# Sheet1.net
KiCad netlist of a schematic drawn in Altium Designer
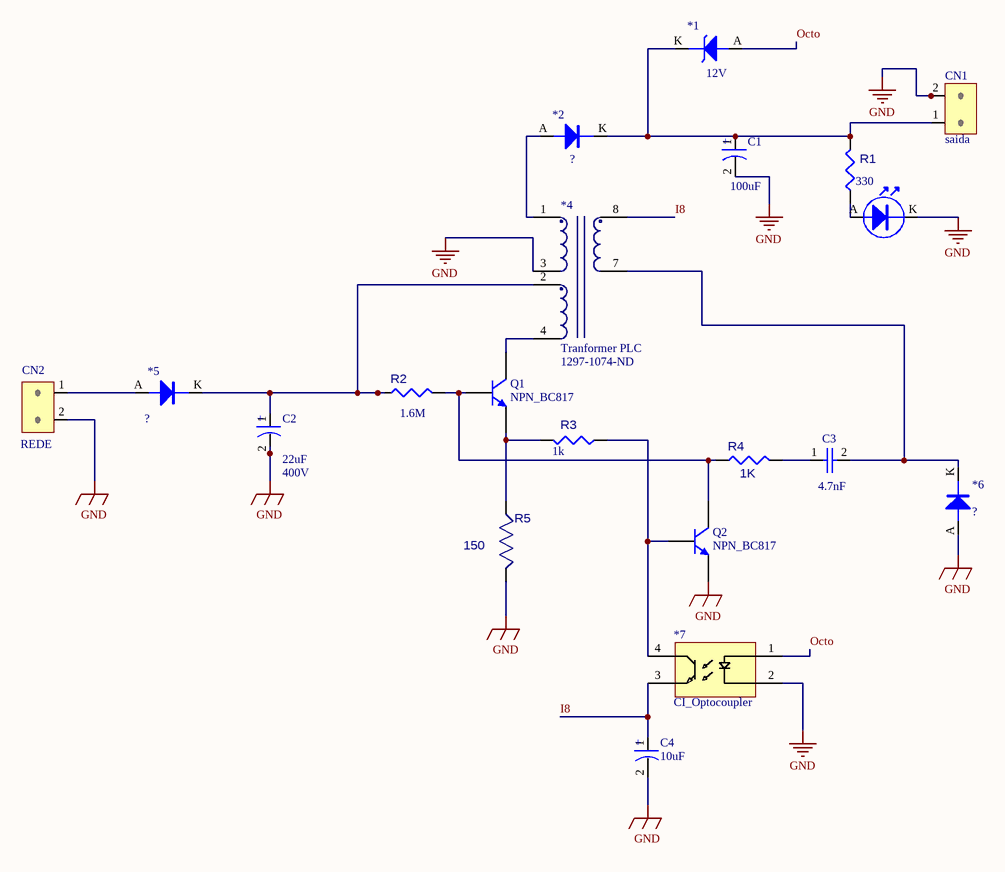
[diagram p0: Sheet1.SchDoc]

(export (version "E")
  (design (tool "Eeschema 10.0.6"))
  (components
    (comp (ref "*1")
      (value "12V")
      (footprint "DIO_PTH_DO35")
      (fields (field (name "Comment") "DIO_ZENER_DO35"))
      (libsource (lib "i9Library_Altium") (part "DIO_ZENER_DO35"))
    )
    (comp (ref "*2")
      (value "?")
      (footprint "DIO_PTH_DO41")
      (fields (field (name "Comment") "DIO_PTH_1N4007"))
      (libsource (lib "i9Library_Altium") (part "DIO_PTH_1N4007"))
    )
    (comp (ref "*3")
      (value "LED_AXIAL_5MM")
      (footprint "LED_Axial_5mm")
      (libsource (lib "i9Library_Altium") (part "LED_AXIAL_5MM"))
    )
    (comp (ref "*4")
      (value "Tranformer PLC")
      (footprint "DIV_TRAFO PLC")
      (fields (field (name "SUPPLIER PART NUMBER 1") "1297-1074-ND"))
      (libsource (lib "i9Library_Altium") (part "Tranformer PLC"))
    )
    (comp (ref "*5")
      (value "?")
      (footprint "DIO_SMD_SOD323")
      (fields (field (name "Comment") "DIO_SMD_1N4148"))
      (libsource (lib "i9Library_Altium") (part "DIO_SMD_1N4148"))
    )
    (comp (ref "*6")
      (value "?")
      (footprint "DIO_PTH_DO41")
      (fields (field (name "Comment") "DIO_PTH_1N4007"))
      (libsource (lib "i9Library_Altium") (part "DIO_PTH_1N4007"))
    )
    (comp (ref "*7")
      (value "CI_Optocoupler")
      (footprint "SFH6106")
      (libsource (lib "i9Library_Altium") (part "CI_Optocoupler"))
    )
    (comp (ref "C1")
      (value "100uF")
      (footprint "CAP_ALU_RADIAL_5MM")
      (description "PTH Radial Electrolytic Capacitor")
      (fields (field (name "Comment") "Electrolytic Capacitor"))
      (libsource (lib "i9Library_Altium") (part "CAP_ALU_RADIAL_5MM"))
    )
    (comp (ref "C2")
      (value "22uF")
      (footprint "CAP_ALU_RADIAL_5MM")
      (description "PTH Radial Electrolytic Capacitor")
      (fields (field (name "TENSÃO") "400V") (field (name "Comment") "Electrolytic Capacitor"))
      (libsource (lib "i9Library_Altium") (part "CAP_ALU_RADIAL_5MM"))
    )
    (comp (ref "C3")
      (value "4.7nF")
      (footprint "CAP_POL_RADIAL_16MM")
      (description "PTH Radial Polyester Capacitor")
      (fields (field (name "Comment") "CAP_POL_RADIAL_16MM"))
      (libsource (lib "i9Library_Altium") (part "CAP_POL_RADIAL_16MM"))
    )
    (comp (ref "C4")
      (value "10uF")
      (footprint "CAP_ALU_RADIAL_5MM")
      (description "PTH Radial Electrolytic Capacitor")
      (libsource (lib "i9Library_Altium") (part "CAP_ALU_RADIAL_5MM"))
    )
    (comp (ref "CN1")
      (value "saida")
      (footprint "CN_KRE_2")
      (description "MKDS_2")
      (libsource (lib "") (part "CN_MKDS_2_1"))
    )
    (comp (ref "CN2")
      (value "?")
      (footprint "REDE")
      (description "MKDS_2")
      (libsource (lib "i9Library_Altium") (part "CN_MKDS_2"))
    )
    (comp (ref "Q1")
      (value "NPN_BC817")
      (footprint "HEADER_1X3")
      (libsource (lib "i9Library_Altium") (part "NPN_BC817"))
    )
    (comp (ref "Q2")
      (value "NPN_BC817")
      (footprint "HEADER_1X3")
      (libsource (lib "i9Library_Altium") (part "NPN_BC817"))
    )
    (comp (ref "R1")
      (value "330")
      (footprint "RES_PTH_7.62MM")
      (description "Pin Through Hole Resistor 7.62mm")
      (libsource (lib "i9Library_Altium") (part "RES_PTH_7.62MM"))
    )
    (comp (ref "R2")
      (value "1.6M")
      (footprint "RES_PTH_7.62MM")
      (description "Pin Through Hole Resistor 7.62mm")
      (libsource (lib "i9Library_Altium") (part "RES_PTH_7.62MM"))
    )
    (comp (ref "R3")
      (value "1k")
      (footprint "RES_PTH_7.62MM")
      (description "Pin Through Hole Resistor 7.62mm")
      (libsource (lib "i9Library_Altium") (part "RES_PTH_7.62MM"))
    )
    (comp (ref "R4")
      (value "?")
      (footprint "1K")
      (description "Pin Through Hole Resistor 7.62mm")
      (libsource (lib "i9Library_Altium") (part "RES_PTH_7.62MM"))
    )
    (comp (ref "R5")
      (value "*")
      (footprint "150")
      (description "Pin Through Hole Resistor 300mils/7.62mm")
      (libsource (lib "i9Library_v1.7.5") (part "RES_PTH300"))
    )
  )
  (nets
    (net (code "1") (name "/I8") (class "Default")
      (node (ref "*4") (pin "8") (pinfunction "8_8") (pintype "passive"))
      (node (ref "*7") (pin "3") (pinfunction "C_3") (pintype "passive"))
      (node (ref "C4") (pin "1") (pinfunction "1_1") (pintype "passive"))
    )
    (net (code "2") (name "/Octo") (class "Default")
      (node (ref "*1") (pin "A") (pintype "passive"))
      (node (ref "*7") (pin "1") (pinfunction "A_1") (pintype "passive"))
    )
    (net (code "3") (name "GND") (class "Default")
      (node (ref "*3") (pin "K") (pintype "passive"))
      (node (ref "*4") (pin "3") (pinfunction "3_3") (pintype "passive"))
      (node (ref "*6") (pin "A") (pintype "passive"))
      (node (ref "*7") (pin "2") (pinfunction "C_2") (pintype "passive"))
      (node (ref "C1") (pin "2") (pintype "passive"))
      (node (ref "C2") (pin "2") (pintype "passive"))
      (node (ref "C4") (pin "2") (pintype "passive"))
      (node (ref "CN1") (pin "2") (pinfunction "2_2") (pintype "passive"))
      (node (ref "CN2") (pin "2") (pinfunction "2_2") (pintype "passive"))
      (node (ref "Q2") (pin "2") (pinfunction "E_2") (pintype "passive"))
      (node (ref "R5") (pin "2") (pintype "passive"))
    )
    (net (code "4") (name "Net-(*1-PadK)") (class "Default")
      (node (ref "*1") (pin "K") (pintype "passive"))
      (node (ref "*2") (pin "K") (pintype "passive"))
      (node (ref "C1") (pin "1") (pinfunction "1_1") (pintype "passive"))
      (node (ref "CN1") (pin "1") (pintype "passive"))
      (node (ref "R1") (pin "2") (pinfunction "2_2") (pintype "passive"))
    )
    (net (code "5") (name "Net-(*2-PadA)") (class "Default")
      (node (ref "*2") (pin "A") (pintype "passive"))
      (node (ref "*4") (pin "1") (pinfunction "1_1") (pintype "passive"))
    )
    (net (code "6") (name "Net-(*3-PadA)") (class "Default")
      (node (ref "*3") (pin "A") (pintype "passive"))
      (node (ref "R1") (pin "1") (pinfunction "1_1") (pintype "passive"))
    )
    (net (code "7") (name "Net-(*4-Pad2)") (class "Default")
      (node (ref "*4") (pin "2") (pinfunction "2_2") (pintype "passive"))
      (node (ref "*5") (pin "K") (pintype "passive"))
      (node (ref "C2") (pin "1") (pinfunction "1_1") (pintype "passive"))
      (node (ref "R2") (pin "1") (pinfunction "1_1") (pintype "passive"))
    )
    (net (code "8") (name "Net-(*4-Pad7)") (class "Default")
      (node (ref "*4") (pin "7") (pinfunction "7_7") (pintype "passive"))
      (node (ref "*6") (pin "K") (pintype "passive"))
      (node (ref "C3") (pin "2") (pintype "passive"))
    )
    (net (code "9") (name "Net-(*5-PadA)") (class "Default")
      (node (ref "*5") (pin "A") (pintype "passive"))
      (node (ref "CN2") (pin "1") (pintype "passive"))
    )
    (net (code "10") (name "Net-(*7-E)") (class "Default")
      (node (ref "*7") (pin "4") (pinfunction "E_4") (pintype "passive"))
      (node (ref "Q2") (pin "1") (pinfunction "B_1") (pintype "passive"))
      (node (ref "R3") (pin "1") (pinfunction "1_1") (pintype "passive"))
    )
    (net (code "11") (name "Net-(C3-Pad1)") (class "Default")
      (node (ref "C3") (pin "1") (pintype "passive"))
      (node (ref "R4") (pin "2") (pinfunction "2_2") (pintype "passive"))
    )
    (net (code "12") (name "Net-(Q1-B)") (class "Default")
      (node (ref "Q1") (pin "1") (pinfunction "B_1") (pintype "passive"))
      (node (ref "Q2") (pin "3") (pinfunction "C_3") (pintype "passive"))
      (node (ref "R2") (pin "2") (pinfunction "2_2") (pintype "passive"))
      (node (ref "R4") (pin "1") (pinfunction "1_1") (pintype "passive"))
    )
    (net (code "13") (name "Net-(Q1-C)") (class "Default")
      (node (ref "*4") (pin "4") (pinfunction "4_4") (pintype "passive"))
      (node (ref "Q1") (pin "3") (pinfunction "C_3") (pintype "passive"))
    )
    (net (code "14") (name "Net-(Q1-E)") (class "Default")
      (node (ref "Q1") (pin "2") (pinfunction "E_2") (pintype "passive"))
      (node (ref "R3") (pin "2") (pinfunction "2_2") (pintype "passive"))
      (node (ref "R5") (pin "1") (pintype "passive"))
    )
  )
)
